# carriage_connector.net
KiCad netlist of a schematic drawn in Altium Designer
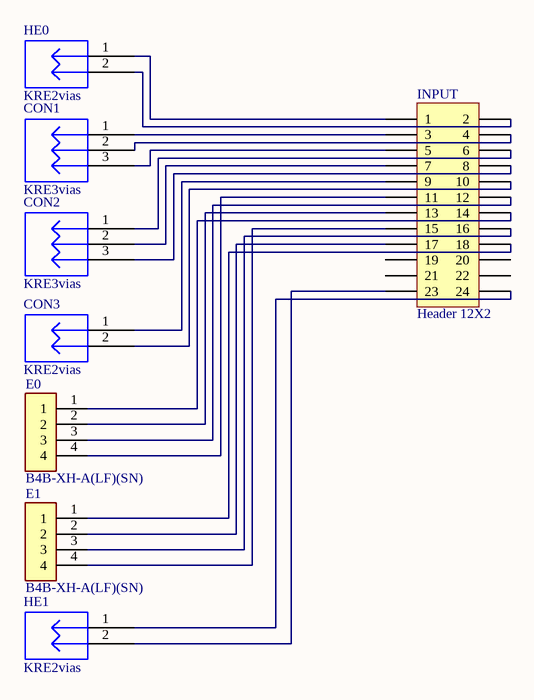
[diagram p0: carriage_connector.SchDoc]

(export (version "E")
  (design (tool "Eeschema 10.0.6"))
  (components
    (comp (ref "CON1")
      (value "KRE3vias")
      (footprint "KRE3-3vias")
      (description "Conector 3 vias")
      (libsource (lib "Altium_Library_Brasil") (part "KRE3vias"))
    )
    (comp (ref "CON2")
      (value "KRE3vias")
      (footprint "KRE3-3vias")
      (description "Conector 3 vias")
      (libsource (lib "Altium_Library_Brasil") (part "KRE3vias"))
    )
    (comp (ref "CON3")
      (value "KRE2vias")
      (footprint "KRE2-2vias")
      (description "Conector 2 vias")
      (libsource (lib "Altium_Library_Brasil") (part "KRE2vias"))
    )
    (comp (ref "E0")
      (value "B4B-XH-A(LF)(SN)")
      (footprint "JST_B4B-XH-A(LF)(SN)")
      (description "Connector Header Through Hole 4 position 0.098 _2.50mm_")
      (fields (field (name "MP") "B4B-XH-A_LF__SN_") (field (name "MF") "JST Sales"))
      (libsource (lib "B4B-XH-A_LF__SN_") (part "B4B-XH-A(LF)(SN)"))
    )
    (comp (ref "E1")
      (value "B4B-XH-A(LF)(SN)")
      (footprint "JST_B4B-XH-A(LF)(SN)")
      (description "Connector Header Through Hole 4 position 0.098 _2.50mm_")
      (fields (field (name "MP") "B4B-XH-A_LF__SN_") (field (name "MF") "JST Sales"))
      (libsource (lib "B4B-XH-A_LF__SN_") (part "B4B-XH-A(LF)(SN)"))
    )
    (comp (ref "HE0")
      (value "KRE2vias")
      (footprint "KRE2-2vias")
      (description "Conector 2 vias")
      (libsource (lib "Altium_Library_Brasil") (part "KRE2vias"))
    )
    (comp (ref "HE1")
      (value "KRE2vias")
      (footprint "KRE2-2vias")
      (description "Conector 2 vias")
      (libsource (lib "Altium_Library_Brasil") (part "KRE2vias"))
    )
    (comp (ref "INPUT")
      (value "Header 12X2")
      (footprint "HDR2X12")
      (description "Header, 12-Pin, Dual row")
      (fields (field (name "PUBLISHER") "Altium Limited"))
      (libsource (lib "Miscellaneous Connectors") (part "Header 12X2"))
    )
  )
  (nets
    (net (code "1") (name "Net-(CON1-Pad1)") (class "Default")
      (node (ref "CON1") (pin "1") (pintype "passive"))
      (node (ref "INPUT") (pin "3") (pinfunction "3_3") (pintype "passive"))
    )
    (net (code "2") (name "Net-(CON1-Pad2)") (class "Default")
      (node (ref "CON1") (pin "2") (pintype "passive"))
      (node (ref "INPUT") (pin "4") (pinfunction "4_4") (pintype "passive"))
    )
    (net (code "3") (name "Net-(CON1-Pad3)") (class "Default")
      (node (ref "CON1") (pin "3") (pintype "passive"))
      (node (ref "INPUT") (pin "5") (pinfunction "5_5") (pintype "passive"))
    )
    (net (code "4") (name "Net-(CON2-Pad1)") (class "Default")
      (node (ref "CON2") (pin "1") (pintype "passive"))
      (node (ref "INPUT") (pin "6") (pinfunction "6_6") (pintype "passive"))
    )
    (net (code "5") (name "Net-(CON2-Pad2)") (class "Default")
      (node (ref "CON2") (pin "2") (pintype "passive"))
      (node (ref "INPUT") (pin "7") (pinfunction "7_7") (pintype "passive"))
    )
    (net (code "6") (name "Net-(CON2-Pad3)") (class "Default")
      (node (ref "CON2") (pin "3") (pintype "passive"))
      (node (ref "INPUT") (pin "8") (pinfunction "8_8") (pintype "passive"))
    )
    (net (code "7") (name "Net-(CON3-Pad1)") (class "Default")
      (node (ref "CON3") (pin "1") (pintype "passive"))
      (node (ref "INPUT") (pin "9") (pinfunction "9_9") (pintype "passive"))
    )
    (net (code "8") (name "Net-(CON3-Pad2)") (class "Default")
      (node (ref "CON3") (pin "2") (pintype "passive"))
      (node (ref "INPUT") (pin "10") (pinfunction "10_10") (pintype "passive"))
    )
    (net (code "9") (name "Net-(E0-Pad1)") (class "Default")
      (node (ref "E0") (pin "1") (pinfunction "1_1") (pintype "passive"))
      (node (ref "INPUT") (pin "14") (pinfunction "14_14") (pintype "passive"))
    )
    (net (code "10") (name "Net-(E0-Pad2)") (class "Default")
      (node (ref "E0") (pin "2") (pinfunction "2_2") (pintype "passive"))
      (node (ref "INPUT") (pin "13") (pinfunction "13_13") (pintype "passive"))
    )
    (net (code "11") (name "Net-(E0-Pad3)") (class "Default")
      (node (ref "E0") (pin "3") (pinfunction "3_3") (pintype "passive"))
      (node (ref "INPUT") (pin "12") (pinfunction "12_12") (pintype "passive"))
    )
    (net (code "12") (name "Net-(E0-Pad4)") (class "Default")
      (node (ref "E0") (pin "4") (pinfunction "4_4") (pintype "passive"))
      (node (ref "INPUT") (pin "11") (pinfunction "11_11") (pintype "passive"))
    )
    (net (code "13") (name "Net-(E1-Pad1)") (class "Default")
      (node (ref "E1") (pin "1") (pinfunction "1_1") (pintype "passive"))
      (node (ref "INPUT") (pin "18") (pinfunction "18_18") (pintype "passive"))
    )
    (net (code "14") (name "Net-(E1-Pad2)") (class "Default")
      (node (ref "E1") (pin "2") (pinfunction "2_2") (pintype "passive"))
      (node (ref "INPUT") (pin "17") (pinfunction "17_17") (pintype "passive"))
    )
    (net (code "15") (name "Net-(E1-Pad3)") (class "Default")
      (node (ref "E1") (pin "3") (pinfunction "3_3") (pintype "passive"))
      (node (ref "INPUT") (pin "16") (pinfunction "16_16") (pintype "passive"))
    )
    (net (code "16") (name "Net-(E1-Pad4)") (class "Default")
      (node (ref "E1") (pin "4") (pinfunction "4_4") (pintype "passive"))
      (node (ref "INPUT") (pin "15") (pinfunction "15_15") (pintype "passive"))
    )
    (net (code "17") (name "Net-(HE0-Pad1)") (class "Default")
      (node (ref "HE0") (pin "1") (pintype "passive"))
      (node (ref "INPUT") (pin "1") (pinfunction "1_1") (pintype "passive"))
    )
    (net (code "18") (name "Net-(HE0-Pad2)") (class "Default")
      (node (ref "HE0") (pin "2") (pintype "passive"))
      (node (ref "INPUT") (pin "2") (pinfunction "2_2") (pintype "passive"))
    )
    (net (code "19") (name "Net-(HE1-Pad1)") (class "Default")
      (node (ref "HE1") (pin "1") (pintype "passive"))
      (node (ref "INPUT") (pin "24") (pinfunction "24_24") (pintype "passive"))
    )
    (net (code "20") (name "Net-(HE1-Pad2)") (class "Default")
      (node (ref "HE1") (pin "2") (pintype "passive"))
      (node (ref "INPUT") (pin "23") (pinfunction "23_23") (pintype "passive"))
    )
    (net (code "21") (name "unconnected-(INPUT-Pad19)") (class "Default")
      (node (ref "INPUT") (pin "19") (pinfunction "19_19") (pintype "passive"))
    )
    (net (code "22") (name "unconnected-(INPUT-Pad20)") (class "Default")
      (node (ref "INPUT") (pin "20") (pinfunction "20_20") (pintype "passive"))
    )
    (net (code "23") (name "unconnected-(INPUT-Pad21)") (class "Default")
      (node (ref "INPUT") (pin "21") (pinfunction "21_21") (pintype "passive"))
    )
    (net (code "24") (name "unconnected-(INPUT-Pad22)") (class "Default")
      (node (ref "INPUT") (pin "22") (pinfunction "22_22") (pintype "passive"))
    )
  )
)
